# wisp-6-mcu.net
KiCad netlist of a schematic drawn in Altium Designer
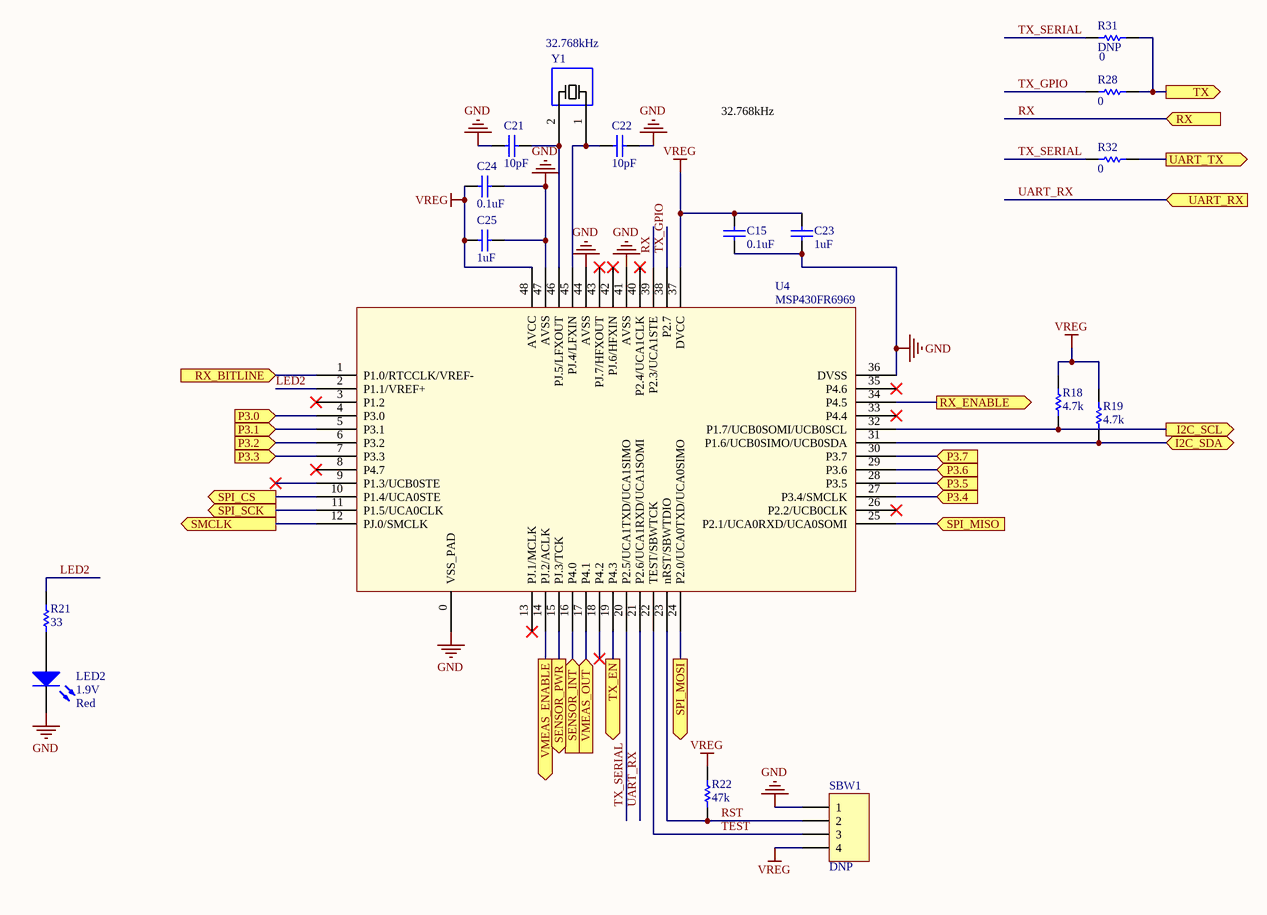
[diagram p0: wisp-6-mcu.SchDoc]

(export (version "E")
  (design (tool "Eeschema 10.0.6"))
  (components
    (comp (ref "C15")
      (value "0.1uF")
      (footprint "0402")
      (description "CAP CER 100nF/0.1UF 10V X5R 0402")
      (fields
        (field (name "DIGI-KEY PART NUMBER") "1276-1022-1-ND")
        (field (name "MANUFACTURER") "Samsung Electro-Mechanics")
      )
      (libsource (lib "WISP6") (part "C-0.1uF-10V-X5R-0402"))
    )
    (comp (ref "C21")
      (value "10pF")
      (footprint "0402")
      (description "CAP CER 10PF 50V C0G/NP0 0402")
      (fields
        (field (name "DIGI-KEY PART NUMBER") "1276-1625-1-ND")
        (field (name "MANUFACTURER") "Samsung Electro-Mechanics")
      )
      (libsource (lib "WISP6") (part "C-10pF-50V-C0G-0402"))
    )
    (comp (ref "C22")
      (value "10pF")
      (footprint "0402")
      (description "CAP CER 10PF 50V C0G/NP0 0402")
      (fields
        (field (name "DIGI-KEY PART NUMBER") "1276-1625-1-ND")
        (field (name "MANUFACTURER") "Samsung Electro-Mechanics")
      )
      (libsource (lib "WISP6") (part "C-10pF-50V-C0G-0402"))
    )
    (comp (ref "C23")
      (value "1uF")
      (footprint "0402")
      (description "CAP CER 1UF 10V X5R 0402")
      (fields
        (field (name "DIGI-KEY PART NUMBER") "1276-1076-1-ND")
        (field (name "MANUFACTURER") "Samsung Electro-Mechanics")
      )
      (libsource (lib "WISP6") (part "C-1uF-10V-X5R-0402"))
    )
    (comp (ref "C24")
      (value "0.1uF")
      (footprint "0402")
      (description "CAP CER 100nF/0.1UF 10V X5R 0402")
      (fields
        (field (name "DIGI-KEY PART NUMBER") "1276-1022-1-ND")
        (field (name "MANUFACTURER") "Samsung Electro-Mechanics")
      )
      (libsource (lib "WISP6") (part "C-0.1uF-10V-X5R-0402"))
    )
    (comp (ref "C25")
      (value "1uF")
      (footprint "0402")
      (description "CAP CER 1UF 10V X5R 0402")
      (fields
        (field (name "DIGI-KEY PART NUMBER") "1276-1076-1-ND")
        (field (name "MANUFACTURER") "Samsung Electro-Mechanics")
      )
      (libsource (lib "WISP6") (part "C-1uF-10V-X5R-0402"))
    )
    (comp (ref "LED2")
      (value "1.9V")
      (footprint "Diode - 0603")
      (description "Red 629nm LED Indication - Discrete 1.9V 0603 (1608 Metric)")
      (fields
        (field (name "DIGI-KEY PART NUMBER") "160-1909-1-ND")
        (field (name "MANUFACTURER") "Lite-On Inc.")
        (field (name "COLOR") "Red")
      )
      (libsource (lib "WISP6") (part "led-red-1V9-0603"))
    )
    (comp (ref "R18")
      (value "4.7k")
      (footprint "0402")
      (description "RES 4.7K OHM 5% 1/16W 0402")
      (fields
        (field (name "MANUFACTURER") "YAGEO")
        (field (name "MANUFACTURER PART NUMBER") "RC0402JR-074K7L")
      )
      (libsource (lib "WISP6") (part "R-4k7-0.063W-5%-0402"))
    )
    (comp (ref "R19")
      (value "4.7k")
      (footprint "0402")
      (description "RES 4.7K OHM 5% 1/16W 0402")
      (fields
        (field (name "MANUFACTURER") "YAGEO")
        (field (name "MANUFACTURER PART NUMBER") "RC0402JR-074K7L")
      )
      (libsource (lib "WISP6") (part "R-4k7-0.063W-5%-0402"))
    )
    (comp (ref "R21")
      (value "33")
      (footprint "0402")
      (description "33 Ohms ±5% 0.063W, 1/16W Chip Resistor 0402 (1005 Metric) Moisture Resistant Thick Film")
      (fields
        (field (name "MANUFACTURER") "YAGEO")
        (field (name "MANUFACTURER PART NUMBER") "RC0402JR-1333RL")
      )
      (libsource (lib "WISP6") (part "R-33-0.063W-5%-0402"))
    )
    (comp (ref "R22")
      (value "47k")
      (footprint "0402")
      (description "RES 47K OHM 5% 1/16W 0402")
      (fields
        (field (name "MANUFACTURER") "YAGEO")
        (field (name "MANUFACTURER PART NUMBER") "RC0402JR-1047KL")
      )
      (libsource (lib "WISP6") (part "R-47k-0.063W-5%-0402"))
    )
    (comp (ref "R28")
      (value "0")
      (footprint "0402")
      (description "RES 0 OHM JUMPER 1/16W 0402")
      (fields
        (field (name "MANUFACTURER") "YAGEO")
        (field (name "MANUFACTURER PART NUMBER") "RC0402JR-070RL")
      )
      (libsource (lib "WISP6") (part "R-0-0.063W-*-0402"))
    )
    (comp (ref "R31")
      (value "DNP")
      (footprint "0402")
      (description "RES 0 OHM JUMPER 1/16W 0402")
      (fields
        (field (name "MANUFACTURER") "YAGEO")
        (field (name "MANUFACTURER PART NUMBER") "RC0402JR-070RL")
        (field (name "NOTE") "0")
      )
      (libsource (lib "WISP6") (part "R-0-0.063W-*-0402"))
    )
    (comp (ref "R32")
      (value "0")
      (footprint "0402")
      (description "RES 0 OHM JUMPER 1/16W 0402")
      (fields
        (field (name "MANUFACTURER") "YAGEO")
        (field (name "MANUFACTURER PART NUMBER") "RC0402JR-070RL")
      )
      (libsource (lib "WISP6") (part "R-0-0.063W-*-0402"))
    )
    (comp (ref "SBW1")
      (value "DNP")
      (footprint "MHDR1X4")
      (description "Header, 4-Pin")
      (fields (field (name "Comment") "MHDR1X4") (field (name "PUBLISHER") "Altium Limited"))
      (libsource (lib "Miscellaneous Connectors") (part "MHDR1X4"))
    )
    (comp (ref "U4")
      (value "MSP430FR6969")
      (footprint "MSP_QFN48_RGZ_PAD0")
      (description "MSP430 CPUXV2 MSP430™ FRAM Microcontroller IC 16-Bit 16MHz 64KB (64K x 8) FRAM 48-VQFN (7x7)")
      (fields
        (field (name "DIGI-KEY PART NUMBER") "296-37918-1-ND")
        (field (name "MANUFACTURER PART NUMBER") "MSP430FR5969IRGZT")
      )
      (libsource (lib "WISP6") (part "MSP430FR596X_586X_RGZ"))
    )
    (comp (ref "Y1")
      (value "32.768kHz")
      (footprint "XTAL [3.20mm x 1.50mm]")
      (description "2-pin XTAL")
      (fields
        (field (name "MANUFACTURER PART NUMBER") "FC-135 32.7680KA-A3")
        (field (name "Comment") "XTAL 2 pin")
      )
      (libsource (lib "WISP6") (part "XTAL_2pin"))
    )
  )
  (nets
    (net (code "1") (name "/I2C_SCL") (class "Default")
      (node (ref "R18") (pin "1") (pinfunction "1_1") (pintype "passive"))
      (node (ref "U4") (pin "32") (pinfunction "P1.7/UCB0SOMI/UCB0SCL_32") (pintype "passive"))
    )
    (net (code "2") (name "/I2C_SDA") (class "Default")
      (node (ref "R19") (pin "1") (pinfunction "1_1") (pintype "passive"))
      (node (ref "U4") (pin "31") (pinfunction "P1.6/UCB0SIMO/UCB0SDA_31") (pintype "passive"))
    )
    (net (code "3") (name "/LED2") (class "Default")
      (node (ref "R21") (pin "2") (pinfunction "2_2") (pintype "passive"))
      (node (ref "U4") (pin "2") (pinfunction "P1.1/VREF+_2") (pintype "passive"))
    )
    (net (code "4") (name "/P3.0") (class "Default")
      (node (ref "U4") (pin "4") (pinfunction "P3.0_4") (pintype "passive"))
    )
    (net (code "5") (name "/P3.1") (class "Default")
      (node (ref "U4") (pin "5") (pinfunction "P3.1_5") (pintype "passive"))
    )
    (net (code "6") (name "/P3.2") (class "Default")
      (node (ref "U4") (pin "6") (pinfunction "P3.2_6") (pintype "passive"))
    )
    (net (code "7") (name "/P3.3") (class "Default")
      (node (ref "U4") (pin "7") (pinfunction "P3.3_7") (pintype "passive"))
    )
    (net (code "8") (name "/P3.4") (class "Default")
      (node (ref "U4") (pin "27") (pinfunction "P3.4/SMCLK_27") (pintype "passive"))
    )
    (net (code "9") (name "/P3.5") (class "Default")
      (node (ref "U4") (pin "28") (pinfunction "P3.5_28") (pintype "passive"))
    )
    (net (code "10") (name "/P3.6") (class "Default")
      (node (ref "U4") (pin "29") (pinfunction "P3.6_29") (pintype "passive"))
    )
    (net (code "11") (name "/P3.7") (class "Default")
      (node (ref "U4") (pin "30") (pinfunction "P3.7_30") (pintype "passive"))
    )
    (net (code "12") (name "/RST") (class "Default")
      (node (ref "R22") (pin "1") (pinfunction "1_1") (pintype "passive"))
      (node (ref "SBW1") (pin "2") (pinfunction "2_2") (pintype "passive"))
      (node (ref "U4") (pin "23") (pinfunction "nRST/SBWTDIO_23") (pintype "passive"))
    )
    (net (code "13") (name "/RX") (class "Default")
      (node (ref "U4") (pin "39") (pinfunction "P2.3/UCA1STE_39") (pintype "passive"))
    )
    (net (code "14") (name "/RX_BITLINE") (class "Default")
      (node (ref "U4") (pin "1") (pinfunction "P1.0/RTCCLK/VREF-_1") (pintype "passive"))
    )
    (net (code "15") (name "/RX_ENABLE") (class "Default")
      (node (ref "U4") (pin "34") (pinfunction "P4.5_34") (pintype "passive"))
    )
    (net (code "16") (name "/SENSOR_INT") (class "Default")
      (node (ref "U4") (pin "16") (pinfunction "P4.0_16") (pintype "passive"))
    )
    (net (code "17") (name "/SENSOR_PWR") (class "Default")
      (node (ref "U4") (pin "15") (pinfunction "PJ.3/TCK_15") (pintype "passive"))
    )
    (net (code "18") (name "/SMCLK") (class "Default")
      (node (ref "U4") (pin "12") (pinfunction "PJ.0/SMCLK_12") (pintype "passive"))
    )
    (net (code "19") (name "/SPI_CS") (class "Default")
      (node (ref "U4") (pin "10") (pinfunction "P1.4/UCA0STE_10") (pintype "passive"))
    )
    (net (code "20") (name "/SPI_MISO") (class "Default")
      (node (ref "U4") (pin "25") (pinfunction "P2.1/UCA0RXD/UCA0SOMI_25") (pintype "passive"))
    )
    (net (code "21") (name "/SPI_MOSI") (class "Default")
      (node (ref "U4") (pin "24") (pinfunction "P2.0/UCA0TXD/UCA0SIMO_24") (pintype "passive"))
    )
    (net (code "22") (name "/SPI_SCK") (class "Default")
      (node (ref "U4") (pin "11") (pinfunction "P1.5/UCA0CLK_11") (pintype "passive"))
    )
    (net (code "23") (name "/TEST") (class "Default")
      (node (ref "SBW1") (pin "3") (pinfunction "3_3") (pintype "passive"))
      (node (ref "U4") (pin "22") (pinfunction "TEST/SBWTCK_22") (pintype "passive"))
    )
    (net (code "24") (name "/TX") (class "Default")
      (node (ref "R28") (pin "1") (pinfunction "1_1") (pintype "passive"))
      (node (ref "R31") (pin "1") (pinfunction "1_1") (pintype "passive"))
    )
    (net (code "25") (name "/TX_EN") (class "Default")
      (node (ref "U4") (pin "19") (pinfunction "P4.3_19") (pintype "passive"))
    )
    (net (code "26") (name "/TX_GPIO") (class "Default")
      (node (ref "R28") (pin "2") (pinfunction "2_2") (pintype "passive"))
      (node (ref "U4") (pin "38") (pinfunction "P2.7_38") (pintype "passive"))
    )
    (net (code "27") (name "/TX_SERIAL") (class "Default")
      (node (ref "R31") (pin "2") (pinfunction "2_2") (pintype "passive"))
      (node (ref "R32") (pin "2") (pinfunction "2_2") (pintype "passive"))
      (node (ref "U4") (pin "20") (pinfunction "P2.5/UCA1TXD/UCA1SIMO_20") (pintype "passive"))
    )
    (net (code "28") (name "/UART_RX") (class "Default")
      (node (ref "U4") (pin "21") (pinfunction "P2.6/UCA1RXD/UCA1SOMI_21") (pintype "passive"))
    )
    (net (code "29") (name "/UART_TX") (class "Default")
      (node (ref "R32") (pin "1") (pinfunction "1_1") (pintype "passive"))
    )
    (net (code "30") (name "/VMEAS_ENABLE") (class "Default")
      (node (ref "U4") (pin "14") (pinfunction "PJ.2/ACLK_14") (pintype "passive"))
    )
    (net (code "31") (name "/VMEAS_OUT") (class "Default")
      (node (ref "U4") (pin "17") (pinfunction "P4.1_17") (pintype "passive"))
    )
    (net (code "32") (name "GND") (class "Default")
      (node (ref "C15") (pin "1") (pinfunction "1_1") (pintype "passive"))
      (node (ref "C21") (pin "1") (pinfunction "1_1") (pintype "passive"))
      (node (ref "C22") (pin "2") (pinfunction "2_2") (pintype "passive"))
      (node (ref "C23") (pin "1") (pinfunction "1_1") (pintype "passive"))
      (node (ref "C24") (pin "2") (pinfunction "2_2") (pintype "passive"))
      (node (ref "C25") (pin "2") (pinfunction "2_2") (pintype "passive"))
      (node (ref "LED2") (pin "2") (pinfunction "K_2") (pintype "passive"))
      (node (ref "SBW1") (pin "1") (pinfunction "1_1") (pintype "passive"))
      (node (ref "U4") (pin "0") (pinfunction "VSS_PAD_0") (pintype "passive"))
      (node (ref "U4") (pin "36") (pinfunction "DVSS_36") (pintype "passive"))
      (node (ref "U4") (pin "41") (pinfunction "AVSS_41") (pintype "passive"))
      (node (ref "U4") (pin "44") (pinfunction "AVSS_44") (pintype "passive"))
      (node (ref "U4") (pin "47") (pinfunction "AVSS_47") (pintype "passive"))
    )
    (net (code "33") (name "Net-(LED2-A)") (class "Default")
      (node (ref "LED2") (pin "1") (pinfunction "A_1") (pintype "passive"))
      (node (ref "R21") (pin "1") (pinfunction "1_1") (pintype "passive"))
    )
    (net (code "34") (name "Net-(U4-PJ.4{slash}LFXIN)") (class "Default")
      (node (ref "C22") (pin "1") (pinfunction "1_1") (pintype "passive"))
      (node (ref "U4") (pin "45") (pinfunction "PJ.4/LFXIN_45") (pintype "passive"))
      (node (ref "Y1") (pin "1") (pinfunction "1_1") (pintype "power_in"))
    )
    (net (code "35") (name "Net-(U4-PJ.5{slash}LFXOUT)") (class "Default")
      (node (ref "C21") (pin "2") (pinfunction "2_2") (pintype "passive"))
      (node (ref "U4") (pin "46") (pinfunction "PJ.5/LFXOUT_46") (pintype "passive"))
      (node (ref "Y1") (pin "2") (pinfunction "2_2") (pintype "power_in"))
    )
    (net (code "36") (name "VREG") (class "Default")
      (node (ref "C15") (pin "2") (pinfunction "2_2") (pintype "passive"))
      (node (ref "C23") (pin "2") (pinfunction "2_2") (pintype "passive"))
      (node (ref "C24") (pin "1") (pinfunction "1_1") (pintype "passive"))
      (node (ref "C25") (pin "1") (pinfunction "1_1") (pintype "passive"))
      (node (ref "R18") (pin "2") (pinfunction "2_2") (pintype "passive"))
      (node (ref "R19") (pin "2") (pinfunction "2_2") (pintype "passive"))
      (node (ref "R22") (pin "2") (pinfunction "2_2") (pintype "passive"))
      (node (ref "SBW1") (pin "4") (pinfunction "4_4") (pintype "passive"))
      (node (ref "U4") (pin "37") (pinfunction "DVCC_37") (pintype "passive"))
      (node (ref "U4") (pin "48") (pinfunction "AVCC_48") (pintype "passive"))
    )
    (net (code "37") (name "unconnected-(U4-P1.2-Pad3)") (class "Default")
      (node (ref "U4") (pin "3") (pinfunction "P1.2_3") (pintype "passive+no_connect"))
    )
    (net (code "38") (name "unconnected-(U4-P1.3{slash}UCB0STE-Pad9)") (class "Default")
      (node (ref "U4") (pin "9") (pinfunction "P1.3/UCB0STE_9") (pintype "passive+no_connect"))
    )
    (net (code "39") (name "unconnected-(U4-P2.2{slash}UCB0CLK-Pad26)") (class "Default")
      (node (ref "U4") (pin "26") (pinfunction "P2.2/UCB0CLK_26") (pintype "passive+no_connect"))
    )
    (net (code "40") (name "unconnected-(U4-P2.4{slash}UCA1CLK-Pad40)") (class "Default")
      (node (ref "U4") (pin "40") (pinfunction "P2.4/UCA1CLK_40") (pintype "passive+no_connect"))
    )
    (net (code "41") (name "unconnected-(U4-P4.2-Pad18)") (class "Default")
      (node (ref "U4") (pin "18") (pinfunction "P4.2_18") (pintype "passive+no_connect"))
    )
    (net (code "42") (name "unconnected-(U4-P4.4-Pad33)") (class "Default")
      (node (ref "U4") (pin "33") (pinfunction "P4.4_33") (pintype "passive+no_connect"))
    )
    (net (code "43") (name "unconnected-(U4-P4.6-Pad35)") (class "Default")
      (node (ref "U4") (pin "35") (pinfunction "P4.6_35") (pintype "passive+no_connect"))
    )
    (net (code "44") (name "unconnected-(U4-P4.7-Pad8)") (class "Default")
      (node (ref "U4") (pin "8") (pinfunction "P4.7_8") (pintype "passive+no_connect"))
    )
    (net (code "45") (name "unconnected-(U4-PJ.1{slash}MCLK-Pad13)") (class "Default")
      (node (ref "U4") (pin "13") (pinfunction "PJ.1/MCLK_13") (pintype "passive+no_connect"))
    )
    (net (code "46") (name "unconnected-(U4-PJ.6{slash}HFXIN-Pad42)") (class "Default")
      (node (ref "U4") (pin "42") (pinfunction "PJ.6/HFXIN_42") (pintype "passive+no_connect"))
    )
    (net (code "47") (name "unconnected-(U4-PJ.7{slash}HFXOUT-Pad43)") (class "Default")
      (node (ref "U4") (pin "43") (pinfunction "PJ.7/HFXOUT_43") (pintype "passive+no_connect"))
    )
  )
)
